# RS485_Soil_Temperature_Sensor_Socket.net
KiCad netlist of a schematic drawn in Altium Designer
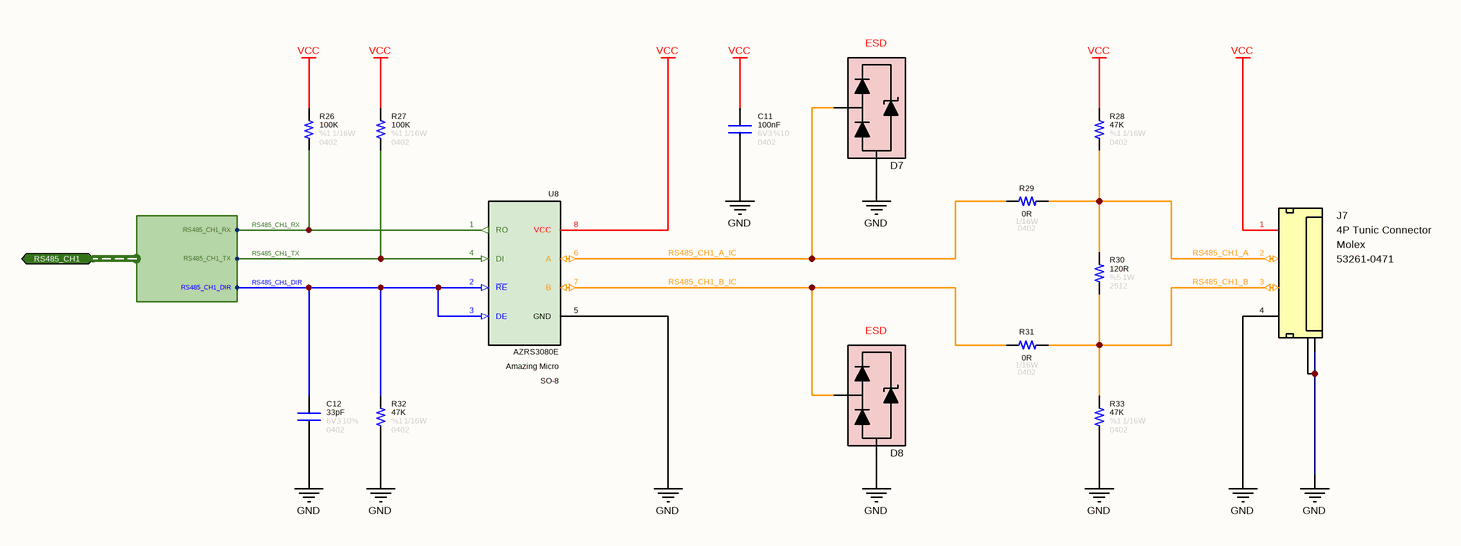
[diagram p0: RS485 Soil Temperature Sensor Socket.SchDoc]

(export (version "E")
  (design (tool "Eeschema 10.0.6"))
  (components
    (comp (ref "C11")
      (value "100nF")
      (footprint "CAPACITOR_0402")
      (description "Capacitor - 100nF [0402-6V3] (Ceramic)")
      (fields
        (field (name "MANUFACTURER PART NUMBER") "04026D104KAT4A")
        (field (name "TOLERANCE") "%10")
        (field (name "VOLTAGE") "6V3")
        (field (name "CASE") "0402")
        (field (name "Comment") "Capacitor - 100nF [0402] (Ceramic)")
      )
      (libsource (lib "P101DA_Library") (part "Capacitor - 100nF [0402-6V3]"))
    )
    (comp (ref "C12")
      (value "33pF")
      (footprint "CAPACITOR_0402")
      (description "Capacitor - 33pF [0402] (Ceramic)")
      (fields
        (field (name "MANUFACTURER PART NUMBER") "C0402C330J9RACAUTO")
        (field (name "TOLERANCE") "10%")
        (field (name "CASE") "0402")
        (field (name "VOLTAGE") "6V3")
      )
      (libsource (lib "P101DA_Library") (part "Capacitor - 33pF [0402-6V3]"))
    )
    (comp (ref "D7")
      (value "0402ESDA-MLP1")
      (footprint "ESD_0402")
      (description "SUPPRESSOR ESD 30VDC 0402 HFREE")
      (libsource (lib "P101DA_Library") (part "Diode - TPD1E05U06DPYR"))
    )
    (comp (ref "D8")
      (value "0402ESDA-MLP1")
      (footprint "ESD_0402")
      (description "SUPPRESSOR ESD 30VDC 0402 HFREE")
      (libsource (lib "P101DA_Library") (part "Diode - TPD1E05U06DPYR"))
    )
    (comp (ref "J7")
      (value "4P SMD Tunic Connector")
      (footprint "Connector_Tunic 4P")
      (description "Mini Tunic Connector with 4P")
      (fields
        (field (name "MANUFACTURER NAME") "Molex")
        (field (name "MANUFACTURER PART NUMBER") "53261-0471")
      )
      (libsource (lib "P101DA_Library") (part "Connector - Mini Tunic 4P (1.25)"))
    )
    (comp (ref "R26")
      (value "100K")
      (footprint "RESISTOR_0402")
      (description "Thick Film Resistors - SMD 1/16 W 100 KOhm 1%")
      (fields
        (field (name "MANUFACTURER PART NUMBER") "CRCW0402100KFKED")
        (field (name "TOLERANCE") "%1")
        (field (name "CASE") "0402")
        (field (name "POWER") "1/16W")
        (field (name "Comment") "100K - 0402 - %1 - 1/16W")
      )
      (libsource (lib "P101DA_Library") (part "Resistor - 100K [0402]"))
    )
    (comp (ref "R27")
      (value "100K")
      (footprint "RESISTOR_0402")
      (description "Thick Film Resistors - SMD 1/16 W 100 KOhm 1%")
      (fields
        (field (name "MANUFACTURER PART NUMBER") "CRCW0402100KFKED")
        (field (name "TOLERANCE") "%1")
        (field (name "CASE") "0402")
        (field (name "POWER") "1/16W")
        (field (name "Comment") "100K - 0402 - %1 - 1/16W")
      )
      (libsource (lib "P101DA_Library") (part "Resistor - 100K [0402]"))
    )
    (comp (ref "R28")
      (value "47K")
      (footprint "RESISTOR_0402")
      (description "Thick Film Resistors - SMD 1/16 W 47 KOhm 1%")
      (fields
        (field (name "MANUFACTURER PART NUMBER") "CRCW040247K0FKED")
        (field (name "TOLERANCE") "%1")
        (field (name "CASE") "0402")
        (field (name "POWER") "1/16W")
        (field (name "Comment") "47K - 0402 - %1 - 1/16W")
      )
      (libsource (lib "P101DA_Library") (part "Resistor - 47K [0402]"))
    )
    (comp (ref "R29")
      (value "0R")
      (footprint "RESISTOR_0402")
      (description "Thick Film Resistors - SMD 1/16 W 0 Ohm")
      (fields
        (field (name "MANUFACTURER PART NUMBER") "CRCW04020000Z0ED")
        (field (name "CASE") "0402")
        (field (name "POWER") "1/16W")
        (field (name "Comment") "0R - 0402 - %1 - 1/16W")
      )
      (libsource (lib "P101DA_Library") (part "Resistor - 0R [0402]"))
    )
    (comp (ref "R30")
      (value "120R")
      (footprint "RESISTOR_2512")
      (description "Thick Film Resistors - SMD 1 W 120 Ohm 5%")
      (fields
        (field (name "MANUFACTURER PART NUMBER") "RC2512JK-07120RL")
        (field (name "TOLERANCE") "%5")
        (field (name "CASE") "2512")
        (field (name "POWER") "1W")
        (field (name "Comment") "120R - 2512 - %5 - 1W")
      )
      (libsource (lib "P101DA_Library") (part "Resistor - 120R [2512]"))
    )
    (comp (ref "R31")
      (value "0R")
      (footprint "RESISTOR_0402")
      (description "Thick Film Resistors - SMD 1/16 W 0 Ohm")
      (fields
        (field (name "MANUFACTURER PART NUMBER") "CRCW04020000Z0ED")
        (field (name "CASE") "0402")
        (field (name "POWER") "1/16W")
        (field (name "Comment") "0R - 0402 - %1 - 1/16W")
      )
      (libsource (lib "P101DA_Library") (part "Resistor - 0R [0402]"))
    )
    (comp (ref "R32")
      (value "47K")
      (footprint "RESISTOR_0402")
      (description "Thick Film Resistors - SMD 1/16 W 47 KOhm 1%")
      (fields
        (field (name "MANUFACTURER PART NUMBER") "CRCW040247K0FKED")
        (field (name "TOLERANCE") "%1")
        (field (name "CASE") "0402")
        (field (name "POWER") "1/16W")
        (field (name "Comment") "47K - 0402 - %1 - 1/16W")
      )
      (libsource (lib "P101DA_Library") (part "Resistor - 47K [0402]"))
    )
    (comp (ref "R33")
      (value "47K")
      (footprint "RESISTOR_0402")
      (description "Thick Film Resistors - SMD 1/16 W 47 KOhm 1%")
      (fields
        (field (name "MANUFACTURER PART NUMBER") "CRCW040247K0FKED")
        (field (name "TOLERANCE") "%1")
        (field (name "CASE") "0402")
        (field (name "POWER") "1/16W")
        (field (name "Comment") "47K - 0402 - %1 - 1/16W")
      )
      (libsource (lib "P101DA_Library") (part "Resistor - 47K [0402]"))
    )
    (comp (ref "U8")
      (value "RS485 Modulator")
      (footprint "SOP-8L (AZRS3080E)")
      (description "Half-duplex RS485 transceiver.")
      (fields
        (field (name "CASE") "SO-8")
        (field (name "MANUFACTURER PART NUMBER") "AZRS3080E")
        (field (name "MANUFACTURER NAME") "Amazing Micro")
      )
      (libsource (lib "P101DA_Library") (part "IC - AZRS3080E"))
    )
  )
  (nets
    (net (code "2") (name "/RS485_CH1_A") (class "Default")
      (node (ref "J7") (pin "2") (pinfunction "Pin-2_2") (pintype "bidirectional"))
      (node (ref "R28") (pin "1") (pinfunction "1_1") (pintype "passive"))
      (node (ref "R29") (pin "1") (pinfunction "1_1") (pintype "passive"))
      (node (ref "R30") (pin "2") (pinfunction "2_2") (pintype "passive"))
    )
    (net (code "3") (name "/RS485_CH1_A_IC") (class "Default")
      (node (ref "D7") (pin "1") (pinfunction "I/O_1") (pintype "passive"))
      (node (ref "R29") (pin "2") (pinfunction "2_2") (pintype "passive"))
      (node (ref "U8") (pin "6") (pinfunction "A_6") (pintype "bidirectional"))
    )
    (net (code "4") (name "/RS485_CH1_B") (class "Default")
      (node (ref "J7") (pin "3") (pinfunction "Pin-3_3") (pintype "bidirectional"))
      (node (ref "R30") (pin "1") (pinfunction "1_1") (pintype "passive"))
      (node (ref "R31") (pin "1") (pinfunction "1_1") (pintype "passive"))
      (node (ref "R33") (pin "2") (pinfunction "2_2") (pintype "passive"))
    )
    (net (code "5") (name "/RS485_CH1_B_IC") (class "Default")
      (node (ref "D8") (pin "1") (pinfunction "I/O_1") (pintype "passive"))
      (node (ref "R31") (pin "2") (pinfunction "2_2") (pintype "passive"))
      (node (ref "U8") (pin "7") (pinfunction "B_7") (pintype "bidirectional"))
    )
    (net (code "6") (name "/RS485_CH1_DIR") (class "Default")
      (node (ref "C12") (pin "2") (pinfunction "2_2") (pintype "passive"))
      (node (ref "R32") (pin "2") (pinfunction "2_2") (pintype "passive"))
      (node (ref "U8") (pin "2") (pinfunction "~{RE}_2") (pintype "input"))
      (node (ref "U8") (pin "3") (pinfunction "DE_3") (pintype "input"))
    )
    (net (code "7") (name "/RS485_CH1_RX") (class "Default")
      (node (ref "R26") (pin "1") (pinfunction "1_1") (pintype "passive"))
      (node (ref "U8") (pin "1") (pinfunction "RO_1") (pintype "output"))
    )
    (net (code "8") (name "/RS485_CH1_TX") (class "Default")
      (node (ref "R27") (pin "1") (pinfunction "1_1") (pintype "passive"))
      (node (ref "U8") (pin "4") (pinfunction "DI_4") (pintype "input"))
    )
    (net (code "10") (name "GND") (class "Default")
      (node (ref "C11") (pin "1") (pinfunction "1_1") (pintype "passive"))
      (node (ref "C12") (pin "1") (pinfunction "1_1") (pintype "passive"))
      (node (ref "D7") (pin "2") (pinfunction "GND_2") (pintype "passive"))
      (node (ref "D8") (pin "2") (pinfunction "GND_2") (pintype "passive"))
      (node (ref "J7") (pin "4") (pinfunction "Pin-4_4") (pintype "power_in"))
      (node (ref "J7") (pin "5") (pinfunction "GND_5") (pintype "passive"))
      (node (ref "J7") (pin "6") (pinfunction "GND_6") (pintype "passive"))
      (node (ref "R32") (pin "1") (pinfunction "1_1") (pintype "passive"))
      (node (ref "R33") (pin "1") (pinfunction "1_1") (pintype "passive"))
      (node (ref "U8") (pin "5") (pinfunction "GND_5") (pintype "passive"))
    )
    (net (code "11") (name "VCC") (class "Default")
      (node (ref "C11") (pin "2") (pinfunction "2_2") (pintype "passive"))
      (node (ref "J7") (pin "1") (pinfunction "Pin-1_1") (pintype "power_in"))
      (node (ref "R26") (pin "2") (pinfunction "2_2") (pintype "passive"))
      (node (ref "R27") (pin "2") (pinfunction "2_2") (pintype "passive"))
      (node (ref "R28") (pin "2") (pinfunction "2_2") (pintype "passive"))
      (node (ref "U8") (pin "8") (pinfunction "VCC_8") (pintype "power_in"))
    )
  )
)
